# ArtNet_Node_v2.net
KiCad netlist of a schematic drawn in EAGLE
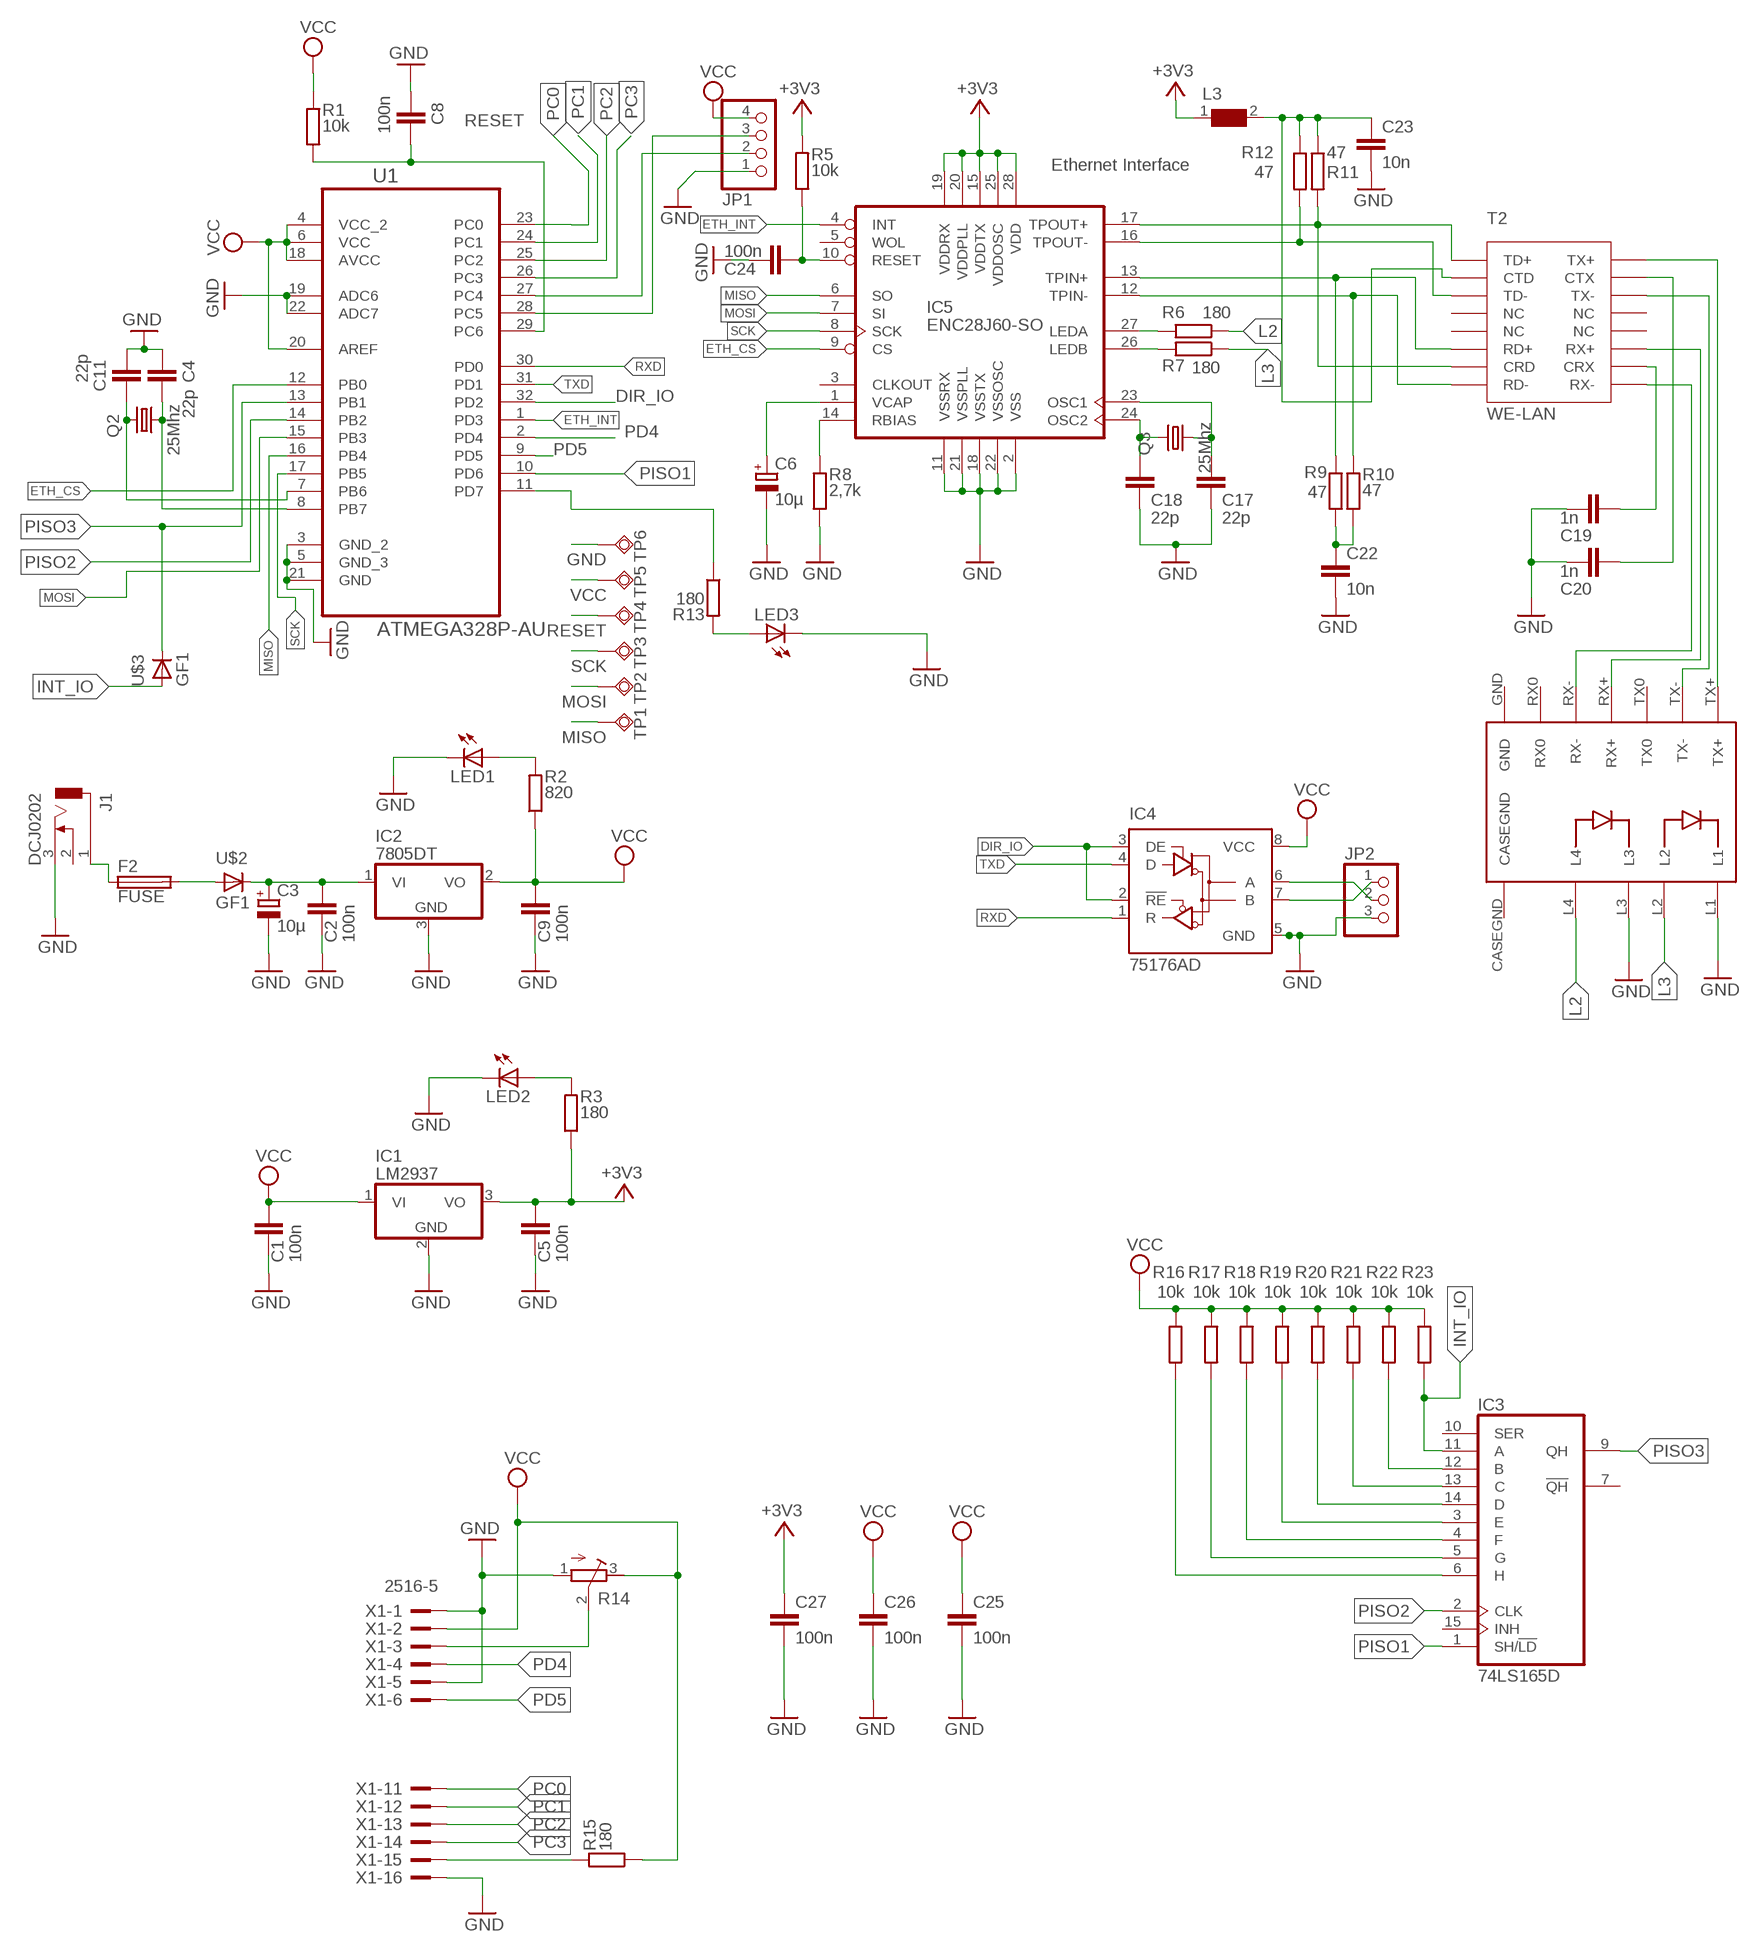
[diagram p0: schematic, sheet 1]

(export (version "E")
  (design (tool "Eeschema 10.0.6"))
  (components
    (comp (ref "C1")
      (value "100n")
      (footprint "eagle-import:C1206")
      (libsource (lib "eagle-import") (part "C-EUC1206"))
    )
    (comp (ref "C2")
      (value "100n")
      (footprint "eagle-import:C1206")
      (libsource (lib "eagle-import") (part "C-EUC1206"))
    )
    (comp (ref "C3")
      (value "10µ")
      (footprint "eagle-import:UD-5X5,8_NICHICON")
      (libsource (lib "eagle-import") (part "CPOL-EUUD-5X5,8"))
    )
    (comp (ref "C4")
      (value "22p")
      (footprint "eagle-import:C1206")
      (libsource (lib "eagle-import") (part "C-EUC1206"))
    )
    (comp (ref "C5")
      (value "100n")
      (footprint "eagle-import:C1206")
      (libsource (lib "eagle-import") (part "C-EUC1206"))
    )
    (comp (ref "C6")
      (value "10µ")
      (footprint "eagle-import:UD-5X5,8_NICHICON")
      (libsource (lib "eagle-import") (part "CPOL-EUUD-5X5,8"))
    )
    (comp (ref "C8")
      (value "100n")
      (footprint "eagle-import:C1206")
      (libsource (lib "eagle-import") (part "C-EUC1206"))
    )
    (comp (ref "C9")
      (value "100n")
      (footprint "eagle-import:C1206")
      (libsource (lib "eagle-import") (part "C-EUC1206"))
    )
    (comp (ref "C11")
      (value "22p")
      (footprint "eagle-import:C1206")
      (libsource (lib "eagle-import") (part "C-EUC1206"))
    )
    (comp (ref "C17")
      (value "22p")
      (footprint "eagle-import:C1206")
      (libsource (lib "eagle-import") (part "C-EUC1206"))
    )
    (comp (ref "C18")
      (value "22p")
      (footprint "eagle-import:C1206")
      (libsource (lib "eagle-import") (part "C-EUC1206"))
    )
    (comp (ref "C19")
      (value "1n")
      (footprint "eagle-import:C1206")
      (libsource (lib "eagle-import") (part "C-EUC1206"))
    )
    (comp (ref "C20")
      (value "1n")
      (footprint "eagle-import:C1206")
      (libsource (lib "eagle-import") (part "C-EUC1206"))
    )
    (comp (ref "C22")
      (value "10n")
      (footprint "eagle-import:C1206")
      (libsource (lib "eagle-import") (part "C-EUC1206"))
    )
    (comp (ref "C23")
      (value "10n")
      (footprint "eagle-import:C1206")
      (libsource (lib "eagle-import") (part "C-EUC1206"))
    )
    (comp (ref "C24")
      (value "100n")
      (footprint "eagle-import:C1206")
      (libsource (lib "eagle-import") (part "C-EUC1206"))
    )
    (comp (ref "C25")
      (value "100n")
      (footprint "eagle-import:C1206")
      (libsource (lib "eagle-import") (part "C-EUC1206"))
    )
    (comp (ref "C26")
      (value "100n")
      (footprint "eagle-import:C1206")
      (libsource (lib "eagle-import") (part "C-EUC1206"))
    )
    (comp (ref "C27")
      (value "100n")
      (footprint "eagle-import:C1206")
      (libsource (lib "eagle-import") (part "C-EUC1206"))
    )
    (comp (ref "F2")
      (value "FUSE")
      (footprint "eagle-import:OMNIBLOK")
      (libsource (lib "eagle-import") (part "SMD-MICRO-FUSE-BLOCK"))
    )
    (comp (ref "IC1")
      (value "LM2937")
      (footprint "eagle-import:TO263-3")
      (libsource (lib "eagle-import") (part "LM2937"))
    )
    (comp (ref "IC2")
      (value "7805DT")
      (footprint "eagle-import:TO252")
      (libsource (lib "eagle-import") (part "78DT05"))
    )
    (comp (ref "IC3")
      (value "74LS165D")
      (footprint "eagle-import:SO16")
      (libsource (lib "eagle-import") (part "74165DLS"))
    )
    (comp (ref "IC4")
      (value "75176AD")
      (footprint "eagle-import:D_R-PDSO-G8")
      (libsource (lib "eagle-import") (part "75176AD"))
    )
    (comp (ref "IC5")
      (value "ENC28J60-SO")
      (footprint "eagle-import:SO28W")
      (libsource (lib "eagle-import") (part "ENC28J60-SO"))
    )
    (comp (ref "J1")
      (value "DCJ0202")
      (footprint "eagle-import:DCJ0202")
      (libsource (lib "eagle-import") (part "DCJ0202"))
    )
    (comp (ref "JP1")
      (value "PINHD-1X4")
      (footprint "eagle-import:1X04")
      (libsource (lib "eagle-import") (part "PINHD-1X4"))
    )
    (comp (ref "JP2")
      (value "PINHD-1X3")
      (footprint "eagle-import:1X03")
      (libsource (lib "eagle-import") (part "PINHD-1X3"))
    )
    (comp (ref "L3")
      (value "WE-SMD_7427930")
      (footprint "eagle-import:WE-SMD_7427930")
      (libsource (lib "eagle-import") (part "WE-SMD_7427930"))
    )
    (comp (ref "LED1")
      (value "LEDSML1206")
      (footprint "eagle-import:SML1206")
      (libsource (lib "eagle-import") (part "LEDSML1206"))
    )
    (comp (ref "LED2")
      (value "LEDSML1206")
      (footprint "eagle-import:SML1206")
      (libsource (lib "eagle-import") (part "LEDSML1206"))
    )
    (comp (ref "LED3")
      (value "LEDSMT1206")
      (footprint "eagle-import:1206")
      (libsource (lib "eagle-import") (part "LEDSMT1206"))
    )
    (comp (ref "Q2")
      (value "25Mhz")
      (footprint "eagle-import:MM20SS")
      (libsource (lib "eagle-import") (part "CRYTALMM20SS"))
    )
    (comp (ref "Q3")
      (value "25Mhz")
      (footprint "eagle-import:MM20SS")
      (libsource (lib "eagle-import") (part "CRYTALMM20SS"))
    )
    (comp (ref "R1")
      (value "10k")
      (footprint "eagle-import:M1206")
      (libsource (lib "eagle-import") (part "R-EU_M1206"))
    )
    (comp (ref "R2")
      (value "820")
      (footprint "eagle-import:M1206")
      (libsource (lib "eagle-import") (part "R-EU_M1206"))
    )
    (comp (ref "R3")
      (value "180")
      (footprint "eagle-import:M1206")
      (libsource (lib "eagle-import") (part "R-EU_M1206"))
    )
    (comp (ref "R5")
      (value "10k")
      (footprint "eagle-import:M1206")
      (libsource (lib "eagle-import") (part "R-EU_M1206"))
    )
    (comp (ref "R6")
      (value "180")
      (footprint "eagle-import:M1206")
      (libsource (lib "eagle-import") (part "R-EU_M1206"))
    )
    (comp (ref "R7")
      (value "180")
      (footprint "eagle-import:M1206")
      (libsource (lib "eagle-import") (part "R-EU_M1206"))
    )
    (comp (ref "R8")
      (value "2,7k")
      (footprint "eagle-import:M1206")
      (libsource (lib "eagle-import") (part "R-EU_M1206"))
    )
    (comp (ref "R9")
      (value "47")
      (footprint "eagle-import:M1206")
      (libsource (lib "eagle-import") (part "R-EU_M1206"))
    )
    (comp (ref "R10")
      (value "47")
      (footprint "eagle-import:M1206")
      (libsource (lib "eagle-import") (part "R-EU_M1206"))
    )
    (comp (ref "R11")
      (value "47")
      (footprint "eagle-import:M1206")
      (libsource (lib "eagle-import") (part "R-EU_M1206"))
    )
    (comp (ref "R12")
      (value "47")
      (footprint "eagle-import:M1206")
      (libsource (lib "eagle-import") (part "R-EU_M1206"))
    )
    (comp (ref "R13")
      (value "180")
      (footprint "eagle-import:M1206")
      (libsource (lib "eagle-import") (part "R-EU_M1206"))
    )
    (comp (ref "R14")
      (value "R-TRIMMTS63X")
      (footprint "eagle-import:RTRIMTS63X")
      (libsource (lib "eagle-import") (part "R-TRIMMTS63X"))
    )
    (comp (ref "R15")
      (value "180")
      (footprint "eagle-import:M1206")
      (libsource (lib "eagle-import") (part "R-EU_M1206"))
    )
    (comp (ref "R16")
      (value "10k")
      (footprint "eagle-import:M1206")
      (libsource (lib "eagle-import") (part "R-EU_M1206"))
    )
    (comp (ref "R17")
      (value "10k")
      (footprint "eagle-import:M1206")
      (libsource (lib "eagle-import") (part "R-EU_M1206"))
    )
    (comp (ref "R18")
      (value "10k")
      (footprint "eagle-import:M1206")
      (libsource (lib "eagle-import") (part "R-EU_M1206"))
    )
    (comp (ref "R19")
      (value "10k")
      (footprint "eagle-import:M1206")
      (libsource (lib "eagle-import") (part "R-EU_M1206"))
    )
    (comp (ref "R20")
      (value "10k")
      (footprint "eagle-import:M1206")
      (libsource (lib "eagle-import") (part "R-EU_M1206"))
    )
    (comp (ref "R21")
      (value "10k")
      (footprint "eagle-import:M1206")
      (libsource (lib "eagle-import") (part "R-EU_M1206"))
    )
    (comp (ref "R22")
      (value "10k")
      (footprint "eagle-import:M1206")
      (libsource (lib "eagle-import") (part "R-EU_M1206"))
    )
    (comp (ref "R23")
      (value "10k")
      (footprint "eagle-import:M1206")
      (libsource (lib "eagle-import") (part "R-EU_M1206"))
    )
    (comp (ref "T2")
      (value "WE-LAN")
      (footprint "eagle-import:WE-LAN_10_100_BASETX_7490100111")
      (libsource (lib "eagle-import") (part "WE-LAN_10/100_BASETX_7490100111"))
    )
    (comp (ref "TP1")
      (value "TPSQTP20SQ")
      (footprint "eagle-import:TP20SQ")
      (libsource (lib "eagle-import") (part "TPSQTP20SQ"))
    )
    (comp (ref "TP2")
      (value "TPSQTP20SQ")
      (footprint "eagle-import:TP20SQ")
      (libsource (lib "eagle-import") (part "TPSQTP20SQ"))
    )
    (comp (ref "TP3")
      (value "TPSQTP20SQ")
      (footprint "eagle-import:TP20SQ")
      (libsource (lib "eagle-import") (part "TPSQTP20SQ"))
    )
    (comp (ref "TP4")
      (value "TPSQTP20SQ")
      (footprint "eagle-import:TP20SQ")
      (libsource (lib "eagle-import") (part "TPSQTP20SQ"))
    )
    (comp (ref "TP5")
      (value "TPSQTP20SQ")
      (footprint "eagle-import:TP20SQ")
      (libsource (lib "eagle-import") (part "TPSQTP20SQ"))
    )
    (comp (ref "TP6")
      (value "TPSQTP20SQ")
      (footprint "eagle-import:TP20SQ")
      (libsource (lib "eagle-import") (part "TPSQTP20SQ"))
    )
    (comp (ref "U$1")
      (value "1XRJ45_MM_JACK")
      (footprint "eagle-import:1XRJ45_MM_JACK")
      (libsource (lib "eagle-import") (part "1XRJ45_MM_JACK"))
    )
    (comp (ref "U$2")
      (value "GF1")
      (footprint "eagle-import:SMA-DO214AC")
      (libsource (lib "eagle-import") (part "GF1"))
    )
    (comp (ref "U$3")
      (value "GF1")
      (footprint "eagle-import:SMA-DO214AC")
      (libsource (lib "eagle-import") (part "GF1"))
    )
    (comp (ref "U1")
      (value "ATMEGA328P-AU")
      (footprint "eagle-import:QFP80P900X900X120-32N")
      (libsource (lib "eagle-import") (part "ATMEGA328P-AU"))
    )
    (comp (ref "X1")
      (value "2516-5")
      (footprint "eagle-import:PAK100_2500-5-16")
      (fields (field (name "MPN") "D2516-5002-AR"))
      (libsource (lib "eagle-import") (part "2516-5"))
    )
  )
  (nets
    (net (code "1") (name "+3V3") (class "Default")
      (node (ref "C27") (pin "1") (pinfunction "1_1") (pintype "passive"))
      (node (ref "C5") (pin "2") (pinfunction "2_2") (pintype "passive"))
      (node (ref "IC1") (pin "3") (pinfunction "VO_3") (pintype "passive"))
      (node (ref "IC5") (pin "15") (pinfunction "VDDTX_15") (pintype "power_in"))
      (node (ref "IC5") (pin "19") (pinfunction "VDDRX_19") (pintype "power_in"))
      (node (ref "IC5") (pin "20") (pinfunction "VDDPLL_20") (pintype "power_in"))
      (node (ref "IC5") (pin "25") (pinfunction "VDDOSC_25") (pintype "power_in"))
      (node (ref "IC5") (pin "28") (pinfunction "VDD_28") (pintype "power_in"))
      (node (ref "L3") (pin "1") (pinfunction "1_1") (pintype "passive"))
      (node (ref "R3") (pin "1") (pinfunction "1_1") (pintype "passive"))
      (node (ref "R5") (pin "2") (pinfunction "2_2") (pintype "passive"))
    )
    (net (code "2") (name "/RESET") (class "Default")
      (node (ref "C8") (pin "1") (pinfunction "1_1") (pintype "passive"))
      (node (ref "R1") (pin "1") (pinfunction "1_1") (pintype "passive"))
      (node (ref "TP4") (pin "TP") (pinfunction "TP_TP") (pintype "input"))
      (node (ref "U1") (pin "29") (pinfunction "PC6_29") (pintype "bidirectional"))
    )
    (net (code "3") (name "DIR_IO") (class "Default")
      (node (ref "IC4") (pin "2") (pinfunction "~{RE}_2") (pintype "input"))
      (node (ref "IC4") (pin "3") (pinfunction "DE_3") (pintype "input"))
      (node (ref "U1") (pin "32") (pinfunction "PD2_32") (pintype "output"))
    )
    (net (code "4") (name "ETH_CS") (class "Default")
      (node (ref "IC5") (pin "9") (pinfunction "CS_9") (pintype "input"))
      (node (ref "U1") (pin "12") (pinfunction "PB0_12") (pintype "bidirectional"))
    )
    (net (code "5") (name "ETH_INT") (class "Default")
      (node (ref "IC5") (pin "4") (pinfunction "INT_4") (pintype "output"))
      (node (ref "U1") (pin "1") (pinfunction "PD3_1") (pintype "bidirectional"))
    )
    (net (code "6") (name "GND") (class "Default")
      (node (ref "C1") (pin "1") (pinfunction "1_1") (pintype "passive"))
      (node (ref "C11") (pin "2") (pinfunction "2_2") (pintype "passive"))
      (node (ref "C17") (pin "1") (pinfunction "1_1") (pintype "passive"))
      (node (ref "C18") (pin "1") (pinfunction "1_1") (pintype "passive"))
      (node (ref "C19") (pin "2") (pinfunction "2_2") (pintype "passive"))
      (node (ref "C2") (pin "1") (pinfunction "1_1") (pintype "passive"))
      (node (ref "C20") (pin "2") (pinfunction "2_2") (pintype "passive"))
      (node (ref "C22") (pin "2") (pinfunction "2_2") (pintype "passive"))
      (node (ref "C23") (pin "2") (pinfunction "2_2") (pintype "passive"))
      (node (ref "C24") (pin "1") (pinfunction "1_1") (pintype "passive"))
      (node (ref "C25") (pin "1") (pinfunction "1_1") (pintype "passive"))
      (node (ref "C26") (pin "2") (pinfunction "2_2") (pintype "passive"))
      (node (ref "C27") (pin "2") (pinfunction "2_2") (pintype "passive"))
      (node (ref "C3") (pin "-") (pinfunction "-_-") (pintype "passive"))
      (node (ref "C4") (pin "2") (pinfunction "2_2") (pintype "passive"))
      (node (ref "C5") (pin "1") (pinfunction "1_1") (pintype "passive"))
      (node (ref "C6") (pin "-") (pinfunction "-_-") (pintype "passive"))
      (node (ref "C8") (pin "2") (pinfunction "2_2") (pintype "passive"))
      (node (ref "C9") (pin "1") (pinfunction "1_1") (pintype "passive"))
      (node (ref "IC1") (pin "2") (pinfunction "GND_2") (pintype "passive"))
      (node (ref "IC2") (pin "3") (pinfunction "GND_3") (pintype "passive"))
      (node (ref "IC4") (pin "5") (pinfunction "GND_5") (pintype "power_in"))
      (node (ref "IC5") (pin "11") (pinfunction "VSSRX_11") (pintype "power_in"))
      (node (ref "IC5") (pin "18") (pinfunction "VSSTX_18") (pintype "power_in"))
      (node (ref "IC5") (pin "2") (pinfunction "VSS_2") (pintype "power_in"))
      (node (ref "IC5") (pin "21") (pinfunction "VSSPLL_21") (pintype "power_in"))
      (node (ref "IC5") (pin "22") (pinfunction "VSSOSC_22") (pintype "power_in"))
      (node (ref "J1") (pin "3") (pinfunction "3_3") (pintype "passive"))
      (node (ref "JP1") (pin "1") (pinfunction "1_1") (pintype "passive"))
      (node (ref "JP2") (pin "3") (pinfunction "3_3") (pintype "passive"))
      (node (ref "LED1") (pin "C") (pinfunction "C_C") (pintype "passive"))
      (node (ref "LED2") (pin "C") (pinfunction "C_C") (pintype "passive"))
      (node (ref "LED3") (pin "C") (pinfunction "C_C") (pintype "passive"))
      (node (ref "R14") (pin "1") (pinfunction "E_1") (pintype "passive"))
      (node (ref "R8") (pin "1") (pinfunction "1_1") (pintype "passive"))
      (node (ref "TP6") (pin "TP") (pinfunction "TP_TP") (pintype "input"))
      (node (ref "U$1") (pin "L1") (pinfunction "L1_L1") (pintype "bidirectional"))
      (node (ref "U$1") (pin "L3") (pinfunction "L3_L3") (pintype "bidirectional"))
      (node (ref "U1") (pin "19") (pinfunction "ADC6_19") (pintype "input"))
      (node (ref "U1") (pin "21") (pinfunction "GND_21") (pintype "passive"))
      (node (ref "U1") (pin "22") (pinfunction "ADC7_22") (pintype "input"))
      (node (ref "U1") (pin "3") (pinfunction "GND_2_3") (pintype "passive"))
      (node (ref "U1") (pin "5") (pinfunction "GND_3_5") (pintype "passive"))
      (node (ref "X1") (pin "1") (pinfunction "KL_1") (pintype "passive"))
      (node (ref "X1") (pin "16") (pinfunction "KL_16") (pintype "passive"))
      (node (ref "X1") (pin "5") (pinfunction "KL_5") (pintype "passive"))
    )
    (net (code "7") (name "INT_IO") (class "Default")
      (node (ref "IC3") (pin "11") (pinfunction "A_11") (pintype "input"))
      (node (ref "R23") (pin "2") (pinfunction "2_2") (pintype "passive"))
      (node (ref "U$3") (pin "A") (pinfunction "A_A") (pintype "passive"))
    )
    (net (code "8") (name "L2") (class "Default")
      (node (ref "R6") (pin "1") (pinfunction "1_1") (pintype "passive"))
      (node (ref "U$1") (pin "L4") (pinfunction "L4_L4") (pintype "bidirectional"))
    )
    (net (code "9") (name "L3") (class "Default")
      (node (ref "R7") (pin "1") (pinfunction "1_1") (pintype "passive"))
      (node (ref "U$1") (pin "L2") (pinfunction "L2_L2") (pintype "bidirectional"))
    )
    (net (code "10") (name "MISO") (class "Default")
      (node (ref "IC5") (pin "6") (pinfunction "SO_6") (pintype "open_collector"))
      (node (ref "TP1") (pin "TP") (pinfunction "TP_TP") (pintype "input"))
      (node (ref "U1") (pin "16") (pinfunction "PB4_16") (pintype "bidirectional"))
    )
    (net (code "11") (name "MOSI") (class "Default")
      (node (ref "IC5") (pin "7") (pinfunction "SI_7") (pintype "input"))
      (node (ref "TP2") (pin "TP") (pinfunction "TP_TP") (pintype "input"))
      (node (ref "U1") (pin "15") (pinfunction "PB3_15") (pintype "bidirectional"))
    )
    (net (code "12") (name "Net-(C22-Pad1)") (class "Default")
      (node (ref "C22") (pin "1") (pinfunction "1_1") (pintype "passive"))
      (node (ref "R10") (pin "1") (pinfunction "1_1") (pintype "passive"))
      (node (ref "R9") (pin "1") (pinfunction "1_1") (pintype "passive"))
    )
    (net (code "13") (name "Net-(F2-1)") (class "Default")
      (node (ref "F2") (pin "P$1") (pinfunction "1_P$1") (pintype "passive"))
      (node (ref "J1") (pin "1") (pinfunction "1_1") (pintype "passive"))
    )
    (net (code "14") (name "Net-(F2-2)") (class "Default")
      (node (ref "F2") (pin "P$2") (pinfunction "2_P$2") (pintype "passive"))
      (node (ref "U$2") (pin "A") (pinfunction "A_A") (pintype "passive"))
    )
    (net (code "15") (name "Net-(IC2-VI)") (class "Default")
      (node (ref "C2") (pin "2") (pinfunction "2_2") (pintype "passive"))
      (node (ref "C3") (pin "+") (pinfunction "+_+") (pintype "passive"))
      (node (ref "IC2") (pin "1") (pinfunction "VI_1") (pintype "input"))
      (node (ref "U$2") (pin "K") (pinfunction "C_K") (pintype "passive"))
    )
    (net (code "16") (name "Net-(IC3A-B)") (class "Default")
      (node (ref "IC3") (pin "12") (pinfunction "B_12") (pintype "input"))
      (node (ref "R22") (pin "2") (pinfunction "2_2") (pintype "passive"))
    )
    (net (code "17") (name "Net-(IC3A-C)") (class "Default")
      (node (ref "IC3") (pin "13") (pinfunction "C_13") (pintype "input"))
      (node (ref "R21") (pin "2") (pinfunction "2_2") (pintype "passive"))
    )
    (net (code "18") (name "Net-(IC3A-D)") (class "Default")
      (node (ref "IC3") (pin "14") (pinfunction "D_14") (pintype "input"))
      (node (ref "R20") (pin "2") (pinfunction "2_2") (pintype "passive"))
    )
    (net (code "19") (name "Net-(IC3A-E)") (class "Default")
      (node (ref "IC3") (pin "3") (pinfunction "E_3") (pintype "input"))
      (node (ref "R19") (pin "2") (pinfunction "2_2") (pintype "passive"))
    )
    (net (code "20") (name "Net-(IC3A-F)") (class "Default")
      (node (ref "IC3") (pin "4") (pinfunction "F_4") (pintype "input"))
      (node (ref "R18") (pin "2") (pinfunction "2_2") (pintype "passive"))
    )
    (net (code "21") (name "Net-(IC3A-G)") (class "Default")
      (node (ref "IC3") (pin "5") (pinfunction "G_5") (pintype "input"))
      (node (ref "R17") (pin "2") (pinfunction "2_2") (pintype "passive"))
    )
    (net (code "22") (name "Net-(IC3A-H)") (class "Default")
      (node (ref "IC3") (pin "6") (pinfunction "H_6") (pintype "input"))
      (node (ref "R16") (pin "2") (pinfunction "2_2") (pintype "passive"))
    )
    (net (code "23") (name "Net-(IC4-A)") (class "Default")
      (node (ref "IC4") (pin "6") (pinfunction "A_6") (pintype "output"))
      (node (ref "JP2") (pin "2") (pinfunction "2_2") (pintype "passive"))
    )
    (net (code "24") (name "Net-(IC4-B)") (class "Default")
      (node (ref "IC4") (pin "7") (pinfunction "B_7") (pintype "output"))
      (node (ref "JP2") (pin "1") (pinfunction "1_1") (pintype "passive"))
    )
    (net (code "25") (name "Net-(IC5-LEDA)") (class "Default")
      (node (ref "IC5") (pin "27") (pinfunction "LEDA_27") (pintype "output"))
      (node (ref "R6") (pin "2") (pinfunction "2_2") (pintype "passive"))
    )
    (net (code "26") (name "Net-(IC5-LEDB)") (class "Default")
      (node (ref "IC5") (pin "26") (pinfunction "LEDB_26") (pintype "output"))
      (node (ref "R7") (pin "2") (pinfunction "2_2") (pintype "passive"))
    )
    (net (code "27") (name "Net-(IC5-OSC1)") (class "Default")
      (node (ref "C17") (pin "2") (pinfunction "2_2") (pintype "passive"))
      (node (ref "IC5") (pin "23") (pinfunction "OSC1_23") (pintype "input"))
      (node (ref "Q3") (pin "1") (pinfunction "1_1") (pintype "passive"))
    )
    (net (code "28") (name "Net-(IC5-OSC2)") (class "Default")
      (node (ref "C18") (pin "2") (pinfunction "2_2") (pintype "passive"))
      (node (ref "IC5") (pin "24") (pinfunction "OSC2_24") (pintype "output"))
      (node (ref "Q3") (pin "4") (pinfunction "2_4") (pintype "passive"))
    )
    (net (code "29") (name "Net-(IC5-RBIAS)") (class "Default")
      (node (ref "IC5") (pin "14") (pinfunction "RBIAS_14") (pintype "passive"))
      (node (ref "R8") (pin "2") (pinfunction "2_2") (pintype "passive"))
    )
    (net (code "30") (name "Net-(IC5-RESET)") (class "Default")
      (node (ref "C24") (pin "2") (pinfunction "2_2") (pintype "passive"))
      (node (ref "IC5") (pin "10") (pinfunction "RESET_10") (pintype "input"))
      (node (ref "R5") (pin "1") (pinfunction "1_1") (pintype "passive"))
    )
    (net (code "31") (name "Net-(IC5-TPIN+)") (class "Default")
      (node (ref "IC5") (pin "13") (pinfunction "TPIN+_13") (pintype "input"))
      (node (ref "R9") (pin "2") (pinfunction "2_2") (pintype "passive"))
      (node (ref "T2") (pin "6") (pinfunction "RD+_6") (pintype "passive"))
    )
    (net (code "32") (name "Net-(IC5-TPIN-)") (class "Default")
      (node (ref "IC5") (pin "12") (pinfunction "TPIN-_12") (pintype "input"))
      (node (ref "R10") (pin "2") (pinfunction "2_2") (pintype "passive"))
      (node (ref "T2") (pin "8") (pinfunction "RD-_8") (pintype "passive"))
    )
    (net (code "33") (name "Net-(IC5-TPOUT+)") (class "Default")
      (node (ref "IC5") (pin "17") (pinfunction "TPOUT+_17") (pintype "output"))
      (node (ref "R11") (pin "2") (pinfunction "2_2") (pintype "passive"))
      (node (ref "T2") (pin "1") (pinfunction "TD+_1") (pintype "passive"))
      (node (ref "T2") (pin "7") (pinfunction "CRD_7") (pintype "passive"))
    )
    (net (code "34") (name "Net-(IC5-TPOUT-)") (class "Default")
      (node (ref "IC5") (pin "16") (pinfunction "TPOUT-_16") (pintype "output"))
      (node (ref "R12") (pin "2") (pinfunction "2_2") (pintype "passive"))
      (node (ref "T2") (pin "3") (pinfunction "TD-_3") (pintype "passive"))
    )
    (net (code "35") (name "Net-(IC5-VCAP)") (class "Default")
      (node (ref "C6") (pin "+") (pinfunction "+_+") (pintype "passive"))
      (node (ref "IC5") (pin "1") (pinfunction "VCAP_1") (pintype "power_in"))
    )
    (net (code "36") (name "Net-(LED1-PadA)") (class "Default")
      (node (ref "LED1") (pin "A") (pinfunction "A_A") (pintype "passive"))
      (node (ref "R2") (pin "2") (pinfunction "2_2") (pintype "passive"))
    )
    (net (code "37") (name "Net-(LED2-PadA)") (class "Default")
      (node (ref "LED2") (pin "A") (pinfunction "A_A") (pintype "passive"))
      (node (ref "R3") (pin "2") (pinfunction "2_2") (pintype "passive"))
    )
    (net (code "38") (name "Net-(LED3-PadA)") (class "Default")
      (node (ref "LED3") (pin "A") (pinfunction "A_A") (pintype "passive"))
      (node (ref "R13") (pin "2") (pinfunction "2_2") (pintype "passive"))
    )
    (net (code "39") (name "Net-(Q2-2)") (class "Default")
      (node (ref "C11") (pin "1") (pinfunction "1_1") (pintype "passive"))
      (node (ref "Q2") (pin "4") (pinfunction "2_4") (pintype "passive"))
      (node (ref "U1") (pin "7") (pinfunction "PB6_7") (pintype "bidirectional"))
    )
    (net (code "40") (name "Net-(R14-S)") (class "Default")
      (node (ref "R14") (pin "2") (pinfunction "S_2") (pintype "passive"))
      (node (ref "X1") (pin "3") (pinfunction "KL_3") (pintype "passive"))
    )
    (net (code "41") (name "Net-(T2-CRX)") (class "Default")
      (node (ref "C19") (pin "1") (pinfunction "1_1") (pintype "passive"))
      (node (ref "T2") (pin "10") (pinfunction "CRX_10") (pintype "passive"))
    )
    (net (code "42") (name "Net-(T2-CTD)") (class "Default")
      (node (ref "C23") (pin "1") (pinfunction "1_1") (pintype "passive"))
      (node (ref "L3") (pin "2") (pinfunction "2_2") (pintype "passive"))
      (node (ref "R11") (pin "1") (pinfunction "1_1") (pintype "passive"))
      (node (ref "R12") (pin "1") (pinfunction "1_1") (pintype "passive"))
      (node (ref "T2") (pin "2") (pinfunction "CTD_2") (pintype "passive"))
    )
    (net (code "43") (name "Net-(T2-CTX)") (class "Default")
      (node (ref "C20") (pin "1") (pinfunction "1_1") (pintype "passive"))
      (node (ref "T2") (pin "15") (pinfunction "CTX_15") (pintype "passive"))
    )
    (net (code "44") (name "Net-(T2-RX+)") (class "Default")
      (node (ref "T2") (pin "11") (pinfunction "RX+_11") (pintype "passive"))
      (node (ref "U$1") (pin "RX+") (pinfunction "RX+_RX+") (pintype "bidirectional"))
    )
    (net (code "45") (name "Net-(T2-RX-)") (class "Default")
      (node (ref "T2") (pin "9") (pinfunction "RX-_9") (pintype "passive"))
      (node (ref "U$1") (pin "RX-") (pinfunction "RX-_RX-") (pintype "bidirectional"))
    )
    (net (code "46") (name "Net-(T2-TX+)") (class "Default")
      (node (ref "T2") (pin "16") (pinfunction "TX+_16") (pintype "passive"))
      (node (ref "U$1") (pin "TX+") (pinfunction "TX+_TX+") (pintype "bidirectional"))
    )
    (net (code "47") (name "Net-(T2-TX-)") (class "Default")
      (node (ref "T2") (pin "14") (pinfunction "TX-_14") (pintype "passive"))
      (node (ref "U$1") (pin "TX-") (pinfunction "TX-_TX-") (pintype "bidirectional"))
    )
    (net (code "48") (name "Net-(U1-PB7)") (class "Default")
      (node (ref "C4") (pin "1") (pinfunction "1_1") (pintype "passive"))
      (node (ref "Q2") (pin "1") (pinfunction "1_1") (pintype "passive"))
      (node (ref "U1") (pin "8") (pinfunction "PB7_8") (pintype "bidirectional"))
    )
    (net (code "49") (name "Net-(U1-PC4)") (class "Default")
      (node (ref "JP1") (pin "2") (pinfunction "2_2") (pintype "passive"))
      (node (ref "U1") (pin "27") (pinfunction "PC4_27") (pintype "bidirectional"))
    )
    (net (code "50") (name "Net-(U1-PC5)") (class "Default")
      (node (ref "JP1") (pin "3") (pinfunction "3_3") (pintype "passive"))
      (node (ref "U1") (pin "28") (pinfunction "PC5_28") (pintype "bidirectional"))
    )
    (net (code "51") (name "Net-(U1-PD7)") (class "Default")
      (node (ref "R13") (pin "1") (pinfunction "1_1") (pintype "passive"))
      (node (ref "U1") (pin "11") (pinfunction "PD7_11") (pintype "bidirectional"))
    )
    (net (code "52") (name "Net-(X1G-KL)") (class "Default")
      (node (ref "R15") (pin "2") (pinfunction "2_2") (pintype "passive"))
      (node (ref "X1") (pin "15") (pinfunction "KL_15") (pintype "passive"))
    )
    (net (code "53") (name "PC0") (class "Default")
      (node (ref "U1") (pin "23") (pinfunction "PC0_23") (pintype "bidirectional"))
      (node (ref "X1") (pin "11") (pinfunction "KL_11") (pintype "passive"))
    )
    (net (code "54") (name "PC1") (class "Default")
      (node (ref "U1") (pin "24") (pinfunction "PC1_24") (pintype "bidirectional"))
      (node (ref "X1") (pin "12") (pinfunction "KL_12") (pintype "passive"))
    )
    (net (code "55") (name "PC2") (class "Default")
      (node (ref "U1") (pin "25") (pinfunction "PC2_25") (pintype "bidirectional"))
      (node (ref "X1") (pin "13") (pinfunction "KL_13") (pintype "passive"))
    )
    (net (code "56") (name "PC3") (class "Default")
      (node (ref "U1") (pin "26") (pinfunction "PC3_26") (pintype "bidirectional"))
      (node (ref "X1") (pin "14") (pinfunction "KL_14") (pintype "passive"))
    )
    (net (code "57") (name "PD4") (class "Default")
      (node (ref "U1") (pin "2") (pinfunction "PD4_2") (pintype "bidirectional"))
      (node (ref "X1") (pin "4") (pinfunction "KL_4") (pintype "passive"))
    )
    (net (code "58") (name "PD5") (class "Default")
      (node (ref "U1") (pin "9") (pinfunction "PD5_9") (pintype "bidirectional"))
      (node (ref "X1") (pin "6") (pinfunction "KL_6") (pintype "passive"))
    )
    (net (code "59") (name "PISO1") (class "Default")
      (node (ref "IC3") (pin "1") (pinfunction "SH/~{LD}_1") (pintype "input"))
      (node (ref "U1") (pin "10") (pinfunction "PD6_10") (pintype "bidirectional"))
    )
    (net (code "60") (name "PISO2") (class "Default")
      (node (ref "IC3") (pin "2") (pinfunction "CLK_2") (pintype "input"))
      (node (ref "U1") (pin "14") (pinfunction "PB2_14") (pintype "bidirectional"))
    )
    (net (code "61") (name "PISO3") (class "Default")
      (node (ref "IC3") (pin "9") (pinfunction "QH_9") (pintype "output"))
      (node (ref "U$3") (pin "K") (pinfunction "C_K") (pintype "passive"))
      (node (ref "U1") (pin "13") (pinfunction "PB1_13") (pintype "bidirectional"))
    )
    (net (code "62") (name "RXD") (class "Default")
      (node (ref "IC4") (pin "1") (pinfunction "R_1") (pintype "input"))
      (node (ref "U1") (pin "30") (pinfunction "PD0_30") (pintype "bidirectional"))
    )
    (net (code "63") (name "SCK") (class "Default")
      (node (ref "IC5") (pin "8") (pinfunction "SCK_8") (pintype "input"))
      (node (ref "TP3") (pin "TP") (pinfunction "TP_TP") (pintype "input"))
      (node (ref "U1") (pin "17") (pinfunction "PB5_17") (pintype "bidirectional"))
    )
    (net (code "64") (name "TXD") (class "Default")
      (node (ref "IC4") (pin "4") (pinfunction "D_4") (pintype "input"))
      (node (ref "U1") (pin "31") (pinfunction "PD1_31") (pintype "bidirectional"))
    )
    (net (code "65") (name "VCC") (class "Default")
      (node (ref "C1") (pin "2") (pinfunction "2_2") (pintype "passive"))
      (node (ref "C25") (pin "2") (pinfunction "2_2") (pintype "passive"))
      (node (ref "C26") (pin "1") (pinfunction "1_1") (pintype "passive"))
      (node (ref "C9") (pin "2") (pinfunction "2_2") (pintype "passive"))
      (node (ref "IC1") (pin "1") (pinfunction "VI_1") (pintype "input"))
      (node (ref "IC2") (pin "2") (pinfunction "VO_2") (pintype "passive"))
      (node (ref "IC4") (pin "8") (pinfunction "VCC_8") (pintype "power_in"))
      (node (ref "JP1") (pin "4") (pinfunction "4_4") (pintype "passive"))
      (node (ref "R1") (pin "2") (pinfunction "2_2") (pintype "passive"))
      (node (ref "R14") (pin "3") (pinfunction "A_3") (pintype "passive"))
      (node (ref "R15") (pin "1") (pinfunction "1_1") (pintype "passive"))
      (node (ref "R16") (pin "1") (pinfunction "1_1") (pintype "passive"))
      (node (ref "R17") (pin "1") (pinfunction "1_1") (pintype "passive"))
      (node (ref "R18") (pin "1") (pinfunction "1_1") (pintype "passive"))
      (node (ref "R19") (pin "1") (pinfunction "1_1") (pintype "passive"))
      (node (ref "R2") (pin "1") (pinfunction "1_1") (pintype "passive"))
      (node (ref "R20") (pin "1") (pinfunction "1_1") (pintype "passive"))
      (node (ref "R21") (pin "1") (pinfunction "1_1") (pintype "passive"))
      (node (ref "R22") (pin "1") (pinfunction "1_1") (pintype "passive"))
      (node (ref "R23") (pin "1") (pinfunction "1_1") (pintype "passive"))
      (node (ref "TP5") (pin "TP") (pinfunction "TP_TP") (pintype "input"))
      (node (ref "U1") (pin "18") (pinfunction "AVCC_18") (pintype "power_in"))
      (node (ref "U1") (pin "20") (pinfunction "AREF_20") (pintype "input"))
      (node (ref "U1") (pin "4") (pinfunction "VCC_2_4") (pintype "power_in"))
      (node (ref "U1") (pin "6") (pinfunction "VCC_6") (pintype "power_in"))
      (node (ref "X1") (pin "2") (pinfunction "KL_2") (pintype "passive"))
    )
    (net (code "66") (name "unconnected-(IC3A-INH-Pad15)") (class "Default")
      (node (ref "IC3") (pin "15") (pinfunction "INH_15") (pintype "no_connect"))
    )
    (net (code "67") (name "unconnected-(IC3A-SER-Pad10)") (class "Default")
      (node (ref "IC3") (pin "10") (pinfunction "SER_10") (pintype "no_connect"))
    )
    (net (code "68") (name "unconnected-(IC3A-~{QH}-Pad7)") (class "Default")
      (node (ref "IC3") (pin "7") (pinfunction "~{QH}_7") (pintype "output"))
    )
    (net (code "69") (name "unconnected-(IC5-CLKOUT-Pad3)") (class "Default")
      (node (ref "IC5") (pin "3") (pinfunction "CLKOUT_3") (pintype "output"))
    )
    (net (code "70") (name "unconnected-(IC5-WOL-Pad5)") (class "Default")
      (node (ref "IC5") (pin "5") (pinfunction "WOL_5") (pintype "output"))
    )
    (net (code "71") (name "unconnected-(J1-Pad2)") (class "Default")
      (node (ref "J1") (pin "2") (pinfunction "2_2") (pintype "passive"))
    )
    (net (code "72") (name "unconnected-(T2-NC-Pad4)") (class "Default")
      (node (ref "T2") (pin "4") (pinfunction "NC_4") (pintype "passive"))
    )
    (net (code "73") (name "unconnected-(T2-NC-Pad5)") (class "Default")
      (node (ref "T2") (pin "5") (pinfunction "NC_5") (pintype "passive"))
    )
    (net (code "74") (name "unconnected-(T2-NC-Pad12)") (class "Default")
      (node (ref "T2") (pin "12") (pinfunction "NC_12") (pintype "passive"))
    )
    (net (code "75") (name "unconnected-(T2-NC-Pad13)") (class "Default")
      (node (ref "T2") (pin "13") (pinfunction "NC_13") (pintype "passive"))
    )
    (net (code "76") (name "unconnected-(U$1-PadCASEGND)") (class "Default")
      (node (ref "U$1") (pin "CASEGND") (pinfunction "CASEGND_CASEGND") (pintype "bidirectional"))
    )
    (net (code "77") (name "unconnected-(U$1-PadGND)") (class "Default")
      (node (ref "U$1") (pin "GND") (pinfunction "GND_GND") (pintype "bidirectional"))
    )
    (net (code "78") (name "unconnected-(U$1-PadRX0)") (class "Default")
      (node (ref "U$1") (pin "RX0") (pinfunction "RX0_RX0") (pintype "bidirectional"))
    )
    (net (code "79") (name "unconnected-(U$1-PadTX0)") (class "Default")
      (node (ref "U$1") (pin "TX0") (pinfunction "TX0_TX0") (pintype "bidirectional"))
    )
  )
)
